# Planktoscope-Hat.net
KiCad netlist of a schematic drawn in EAGLE
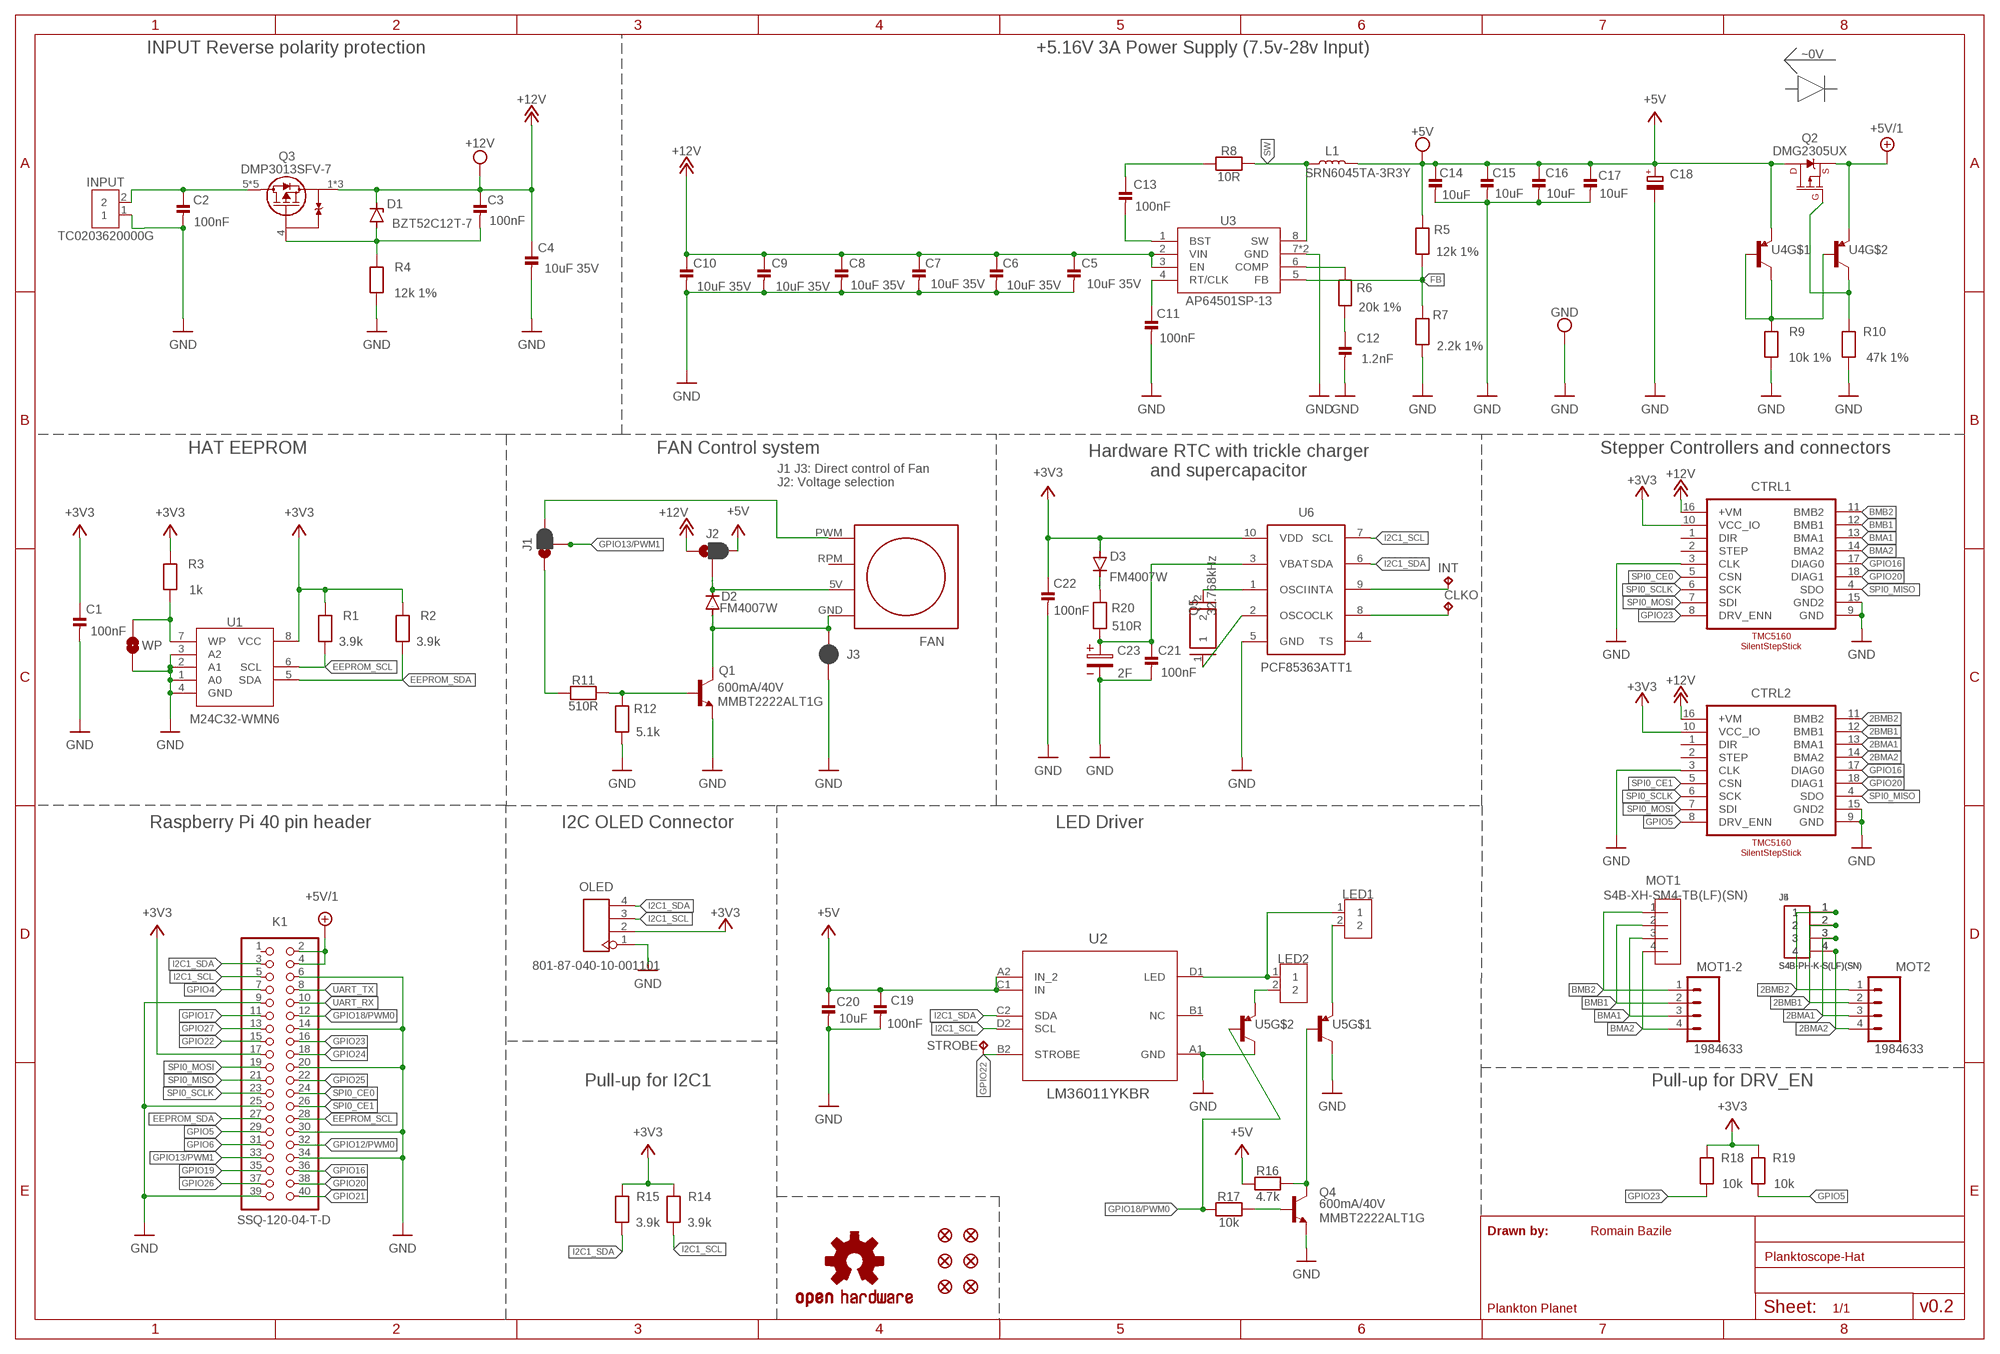
[diagram p0: schematic, sheet 1]

(export (version "E")
  (design (tool "Eeschema 10.0.6"))
  (components
    (comp (ref "+5V")
      (value "TESTPOINTPAD2MM")
      (footprint "eagle-import:TESTPOINT_PAD_2MM")
      (libsource (lib "eagle-import") (part "TESTPOINTPAD2MM"))
    )
    (comp (ref "+12V")
      (value "TESTPOINTPAD2MM")
      (footprint "eagle-import:TESTPOINT_PAD_2MM")
      (libsource (lib "eagle-import") (part "TESTPOINTPAD2MM"))
    )
    (comp (ref "C1")
      (value "100nF")
      (footprint "eagle-import:_0805MP")
      (libsource (lib "eagle-import") (part "CAP_CERAMIC_0805MP"))
    )
    (comp (ref "C2")
      (value "100nF")
      (footprint "eagle-import:_0805MP")
      (libsource (lib "eagle-import") (part "CAP_CERAMIC_0805MP"))
    )
    (comp (ref "C3")
      (value "100nF")
      (footprint "eagle-import:_0805MP")
      (libsource (lib "eagle-import") (part "CAP_CERAMIC_0805MP"))
    )
    (comp (ref "C4")
      (value "10uF 35V")
      (footprint "eagle-import:_0805MP")
      (libsource (lib "eagle-import") (part "CAP_CERAMIC_0805MP"))
    )
    (comp (ref "C5")
      (value "10uF 35V")
      (footprint "eagle-import:_0805MP")
      (libsource (lib "eagle-import") (part "CAP_CERAMIC_0805MP"))
    )
    (comp (ref "C6")
      (value "10uF 35V")
      (footprint "eagle-import:_0805MP")
      (libsource (lib "eagle-import") (part "CAP_CERAMIC_0805MP"))
    )
    (comp (ref "C7")
      (value "10uF 35V")
      (footprint "eagle-import:_0805MP")
      (libsource (lib "eagle-import") (part "CAP_CERAMIC_0805MP"))
    )
    (comp (ref "C8")
      (value "10uF 35V")
      (footprint "eagle-import:_0805MP")
      (libsource (lib "eagle-import") (part "CAP_CERAMIC_0805MP"))
    )
    (comp (ref "C9")
      (value "10uF 35V")
      (footprint "eagle-import:_0805MP")
      (libsource (lib "eagle-import") (part "CAP_CERAMIC_0805MP"))
    )
    (comp (ref "C10")
      (value "10uF 35V")
      (footprint "eagle-import:_0805MP")
      (libsource (lib "eagle-import") (part "CAP_CERAMIC_0805MP"))
    )
    (comp (ref "C11")
      (value "100nF")
      (footprint "eagle-import:_0805MP")
      (libsource (lib "eagle-import") (part "CAP_CERAMIC_0805MP"))
    )
    (comp (ref "C12")
      (value "1.2nF")
      (footprint "eagle-import:_0805MP")
      (libsource (lib "eagle-import") (part "CAP_CERAMIC_0805MP"))
    )
    (comp (ref "C13")
      (value "100nF")
      (footprint "eagle-import:_0805MP")
      (libsource (lib "eagle-import") (part "CAP_CERAMIC_0805MP"))
    )
    (comp (ref "C14")
      (value "10uF")
      (footprint "eagle-import:_0805MP")
      (libsource (lib "eagle-import") (part "CAP_CERAMIC_0805MP"))
    )
    (comp (ref "C15")
      (value "10uF")
      (footprint "eagle-import:_0805MP")
      (libsource (lib "eagle-import") (part "CAP_CERAMIC_0805MP"))
    )
    (comp (ref "C16")
      (value "10uF")
      (footprint "eagle-import:_0805MP")
      (libsource (lib "eagle-import") (part "CAP_CERAMIC_0805MP"))
    )
    (comp (ref "C17")
      (value "10uF")
      (footprint "eagle-import:_0805MP")
      (libsource (lib "eagle-import") (part "CAP_CERAMIC_0805MP"))
    )
    (comp (ref "C18")
      (value "100µF 10VDC")
      (footprint "eagle-import:CAPMP6032X280N")
      (fields (field (name "MPN") "TPSC107K010T0200"))
      (libsource (lib "eagle-import") (part "C-POLTANTALUM-2412(6032-METRIC)_"))
    )
    (comp (ref "C19")
      (value "100nF")
      (footprint "eagle-import:_0805MP")
      (libsource (lib "eagle-import") (part "CAP_CERAMIC_0805MP"))
    )
    (comp (ref "C20")
      (value "10uF")
      (footprint "eagle-import:_0805MP")
      (libsource (lib "eagle-import") (part "CAP_CERAMIC_0805MP"))
    )
    (comp (ref "C21")
      (value "100nF")
      (footprint "eagle-import:_0805MP")
      (libsource (lib "eagle-import") (part "CAP_CERAMIC_0805MP"))
    )
    (comp (ref "C22")
      (value "100nF")
      (footprint "eagle-import:_0805MP")
      (libsource (lib "eagle-import") (part "CAP_CERAMIC_0805MP"))
    )
    (comp (ref "C23")
      (value "2F")
      (footprint "eagle-import:8X3.5X0.9(DXAXB)")
      (fields (field (name "MPN") "SCCR12E105SRB"))
      (libsource (lib "eagle-import") (part "WCAP-PTHT_870135174001_8X8"))
    )
    (comp (ref "CLKO")
      (value "TPB1,27")
      (footprint "eagle-import:B1,27")
      (libsource (lib "eagle-import") (part "TPB1,27"))
    )
    (comp (ref "CTRL1")
      (value "TMC5160_SILENTSTEPSTICK")
      (footprint "eagle-import:TMC5160_STEPSTICK")
      (libsource (lib "eagle-import") (part "TMC5160_SILENTSTEPSTICK"))
    )
    (comp (ref "CTRL2")
      (value "TMC5160_SILENTSTEPSTICK")
      (footprint "eagle-import:TMC5160_STEPSTICK")
      (libsource (lib "eagle-import") (part "TMC5160_SILENTSTEPSTICK"))
    )
    (comp (ref "D1")
      (value "BZT52C12T-7")
      (footprint "eagle-import:SODFL1608X70")
      (libsource (lib "eagle-import") (part "ZENERSODFL(1608-METRIC)_"))
    )
    (comp (ref "D2")
      (value "FM4007W")
      (footprint "eagle-import:DO-214AC")
      (libsource (lib "eagle-import") (part "DIODE-DO-214AC"))
    )
    (comp (ref "D3")
      (value "FM4007W")
      (footprint "eagle-import:DO-214AC")
      (libsource (lib "eagle-import") (part "DIODE-DO-214AC"))
    )
    (comp (ref "FAN")
      (value "40MM_FAN")
      (footprint "eagle-import:40MM_FAN")
      (libsource (lib "eagle-import") (part "40MM_FAN"))
    )
    (comp (ref "FD1")
      (value "FIDUCIAL1X2")
      (footprint "eagle-import:FIDUCIAL-1X2")
      (libsource (lib "eagle-import") (part "FIDUCIAL1X2"))
    )
    (comp (ref "FD2")
      (value "FIDUCIAL1X2")
      (footprint "eagle-import:FIDUCIAL-1X2")
      (libsource (lib "eagle-import") (part "FIDUCIAL1X2"))
    )
    (comp (ref "FD3")
      (value "FIDUCIAL1X2")
      (footprint "eagle-import:FIDUCIAL-1X2")
      (libsource (lib "eagle-import") (part "FIDUCIAL1X2"))
    )
    (comp (ref "FD4")
      (value "FIDUCIAL1X2")
      (footprint "eagle-import:FIDUCIAL-1X2")
      (libsource (lib "eagle-import") (part "FIDUCIAL1X2"))
    )
    (comp (ref "FD5")
      (value "FIDUCIAL1X2")
      (footprint "eagle-import:FIDUCIAL-1X2")
      (libsource (lib "eagle-import") (part "FIDUCIAL1X2"))
    )
    (comp (ref "FD6")
      (value "FIDUCIAL1X2")
      (footprint "eagle-import:FIDUCIAL-1X2")
      (libsource (lib "eagle-import") (part "FIDUCIAL1X2"))
    )
    (comp (ref "GND")
      (value "TESTPOINTPAD2MM")
      (footprint "eagle-import:TESTPOINT_PAD_2MM")
      (libsource (lib "eagle-import") (part "TESTPOINTPAD2MM"))
    )
    (comp (ref "INPUT")
      (value "TC0203620000G")
      (footprint "eagle-import:TERMBLK_508-2N")
      (fields
        (field (name "MANUFACTURER") "TE Connectivity")
        (field (name "MPN") "282837-2")
        (field (name "MPN_1") "TC0203620000G")
      )
      (libsource (lib "eagle-import") (part "2828XX-2282837-2"))
    )
    (comp (ref "INT")
      (value "TPB1,27")
      (footprint "eagle-import:B1,27")
      (libsource (lib "eagle-import") (part "TPB1,27"))
    )
    (comp (ref "J1")
      (value "JUMPER-SMT_3_1-NC_PASTE_SILK")
      (footprint "eagle-import:SMT-JUMPER_3_1-NC_PASTE_SILK")
      (libsource (lib "eagle-import") (part "JUMPER-SMT_3_1-NC_PASTE_SILK"))
    )
    (comp (ref "J2")
      (value "JUMPER-SMT_3_1-NC_PASTE_SILK")
      (footprint "eagle-import:SMT-JUMPER_3_1-NC_PASTE_SILK")
      (libsource (lib "eagle-import") (part "JUMPER-SMT_3_1-NC_PASTE_SILK"))
    )
    (comp (ref "J3")
      (value "JUMPER-SMT_2_NC_PASTE_SILK")
      (footprint "eagle-import:SMT-JUMPER_2_NC_PASTE_SILK")
      (libsource (lib "eagle-import") (part "JUMPER-SMT_2_NC_PASTE_SILK"))
    )
    (comp (ref "J4")
      (value "S4B-PH-K-S(LF)(SN)")
      (footprint "eagle-import:S4B-PH-K-S(LF)(SN)")
      (fields
        (field (name "DIGIKEY_PARTNO") "455-1721-ND")
        (field (name "MANUFACTURER") "JST Sales America Inc.")
        (field (name "CREATED_BY") "PCBLayout.com")
      )
      (libsource (lib "eagle-import") (part "S4B-PH-K-S(LF)(SN)"))
    )
    (comp (ref "J5")
      (value "S4B-PH-K-S(LF)(SN)")
      (footprint "eagle-import:S4B-PH-K-S(LF)(SN)")
      (fields
        (field (name "DIGIKEY_PARTNO") "455-1721-ND")
        (field (name "MANUFACTURER") "JST Sales America Inc.")
        (field (name "CREATED_BY") "PCBLayout.com")
      )
      (libsource (lib "eagle-import") (part "S4B-PH-K-S(LF)(SN)"))
    )
    (comp (ref "K1")
      (value "SSQ-120-04-T-D")
      (footprint "eagle-import:2X20")
      (libsource (lib "eagle-import") (part "PINHD-2X20"))
    )
    (comp (ref "L1")
      (value "SRN6045TA-3R3Y")
      (footprint "eagle-import:SRN6045")
      (libsource (lib "eagle-import") (part "INDUCTOR-SRN6045-33UH"))
    )
    (comp (ref "LED1")
      (value "2828XX-2282834-2")
      (footprint "eagle-import:TERMBLK_254-2N")
      (libsource (lib "eagle-import") (part "2828XX-2282834-2"))
    )
    (comp (ref "LED2")
      (value "2828XX-2282834-2")
      (footprint "eagle-import:TERMBLK_254-2N")
      (libsource (lib "eagle-import") (part "2828XX-2282834-2"))
    )
    (comp (ref "LOGO1")
      (value "OSHW-LOGOL")
      (footprint "eagle-import:OSHW-LOGO-L")
      (libsource (lib "eagle-import") (part "OSHW-LOGOL"))
    )
    (comp (ref "MOT1")
      (value "S4B-XH-SM4-TB(LF)(SN)")
      (footprint "eagle-import:CONN_S4B-XH-SM4-TB_JST")
      (fields
        (field (name "MPN") "S4B-XH-SM4-TB(LF)(SN)")
        (field (name "COPYRIGHT") "Copyright (C) 2018 Accelerated Designs. All rights reserved")
      )
      (libsource (lib "eagle-import") (part "S4B-XH-SM4-TB(LF)(SN)"))
    )
    (comp (ref "MOT1-2")
      (value "1984633")
      (footprint "eagle-import:SCREWTERMINAL-3.5MM-4")
      (libsource (lib "eagle-import") (part "CONN_04SCREW"))
    )
    (comp (ref "MOT2")
      (value "1984633")
      (footprint "eagle-import:SCREWTERMINAL-3.5MM-4")
      (libsource (lib "eagle-import") (part "CONN_04SCREW"))
    )
    (comp (ref "OLED")
      (value "801-87-040-10-001101")
      (footprint "eagle-import:H4-2.54")
      (fields (field (name "MPN") "P125-1104A0BS116A1"))
      (libsource (lib "eagle-import") (part "DIP-BLACK-MALE-HEADER-VERT(4P-2.54)"))
    )
    (comp (ref "Q1")
      (value "600mA/40V")
      (footprint "eagle-import:SOT23-3")
      (fields (field (name "MPN") "MMBT2222ALT1G"))
      (libsource (lib "eagle-import") (part "TRANS_NPN-MMBT2222AL"))
    )
    (comp (ref "Q2")
      (value "DMG2305UX")
      (footprint "eagle-import:SOT23-3")
      (libsource (lib "eagle-import") (part "MOSFET_PCH-DMG2305UX-7"))
    )
    (comp (ref "Q3")
      (value "DMP3013SFV-7")
      (footprint "eagle-import:POWERDI3333-8_UX_DIO")
      (fields
        (field (name "ALT_MANUFACTURE_PART_NUMBER") "SI7101DN")
        (field (name "COPYRIGHT") "Copyright (C) 2018 Accelerated Designs. All rights reserved")
      )
      (libsource (lib "eagle-import") (part "DMP3013SFV-7"))
    )
    (comp (ref "Q4")
      (value "600mA/40V")
      (footprint "eagle-import:SOT23-3")
      (fields (field (name "MPN") "MMBT2222ALT1G"))
      (libsource (lib "eagle-import") (part "TRANS_NPN-MMBT2222AL"))
    )
    (comp (ref "Q5")
      (value "32.768kHz")
      (footprint "eagle-import:XTAL_ABS07-32.768KHZ-T")
      (fields (field (name "MANUFACTURER") "Abracon LLC") (field (name "MPN") "ABS07-32.768KHZ-T "))
      (libsource (lib "eagle-import") (part "ABSO7"))
    )
    (comp (ref "R1")
      (value "3.9k")
      (footprint "eagle-import:_0805MP")
      (libsource (lib "eagle-import") (part "RESISTOR_0805MP"))
    )
    (comp (ref "R2")
      (value "3.9k")
      (footprint "eagle-import:_0805MP")
      (libsource (lib "eagle-import") (part "RESISTOR_0805MP"))
    )
    (comp (ref "R3")
      (value "1k")
      (footprint "eagle-import:_0805MP")
      (libsource (lib "eagle-import") (part "RESISTOR_0805MP"))
    )
    (comp (ref "R4")
      (value "12k 1%")
      (footprint "eagle-import:_0805MP")
      (libsource (lib "eagle-import") (part "RESISTOR_0805MP"))
    )
    (comp (ref "R5")
      (value "12k 1%")
      (footprint "eagle-import:_0805MP")
      (libsource (lib "eagle-import") (part "RESISTOR_0805MP"))
    )
    (comp (ref "R6")
      (value "20k 1%")
      (footprint "eagle-import:_0805MP")
      (libsource (lib "eagle-import") (part "RESISTOR_0805MP"))
    )
    (comp (ref "R7")
      (value "2.2k 1%")
      (footprint "eagle-import:_0805MP")
      (libsource (lib "eagle-import") (part "RESISTOR_0805MP"))
    )
    (comp (ref "R8")
      (value "10R")
      (footprint "eagle-import:_0805MP")
      (libsource (lib "eagle-import") (part "RESISTOR_0805MP"))
    )
    (comp (ref "R9")
      (value "10k 1%")
      (footprint "eagle-import:_0805MP")
      (libsource (lib "eagle-import") (part "RESISTOR_0805MP"))
    )
    (comp (ref "R10")
      (value "47k 1%")
      (footprint "eagle-import:_0805MP")
      (libsource (lib "eagle-import") (part "RESISTOR_0805MP"))
    )
    (comp (ref "R11")
      (value "510R")
      (footprint "eagle-import:_0805MP")
      (libsource (lib "eagle-import") (part "RESISTOR_0805MP"))
    )
    (comp (ref "R12")
      (value "5.1k")
      (footprint "eagle-import:_0805MP")
      (libsource (lib "eagle-import") (part "RESISTOR_0805MP"))
    )
    (comp (ref "R14")
      (value "3.9k")
      (footprint "eagle-import:_0805MP")
      (libsource (lib "eagle-import") (part "RESISTOR_0805MP"))
    )
    (comp (ref "R15")
      (value "3.9k")
      (footprint "eagle-import:_0805MP")
      (libsource (lib "eagle-import") (part "RESISTOR_0805MP"))
    )
    (comp (ref "R16")
      (value "4.7k")
      (footprint "eagle-import:_0805MP")
      (libsource (lib "eagle-import") (part "RESISTOR_0805MP"))
    )
    (comp (ref "R17")
      (value "10k")
      (footprint "eagle-import:_0805MP")
      (libsource (lib "eagle-import") (part "RESISTOR_0805MP"))
    )
    (comp (ref "R18")
      (value "10k")
      (footprint "eagle-import:_0805MP")
      (libsource (lib "eagle-import") (part "RESISTOR_0805MP"))
    )
    (comp (ref "R19")
      (value "10k")
      (footprint "eagle-import:_0805MP")
      (libsource (lib "eagle-import") (part "RESISTOR_0805MP"))
    )
    (comp (ref "R20")
      (value "510R")
      (footprint "eagle-import:_0805MP")
      (libsource (lib "eagle-import") (part "RESISTOR_0805MP"))
    )
    (comp (ref "STROBE")
      (value "TPTP15R")
      (footprint "eagle-import:TP15R")
      (libsource (lib "eagle-import") (part "TPTP15R"))
    )
    (comp (ref "U1")
      (value "M24C32-WMN6")
      (footprint "eagle-import:SO-8_STM")
      (libsource (lib "eagle-import") (part "M24C32-WMN6"))
    )
    (comp (ref "U2")
      (value "LM36011YKBR")
      (footprint "eagle-import:YKB0008AGAG")
      (fields (field (name "MANUFACTURER") "Texas Instruments"))
      (libsource (lib "eagle-import") (part "LM36011YKBR"))
    )
    (comp (ref "U3")
      (value "AP64501SP-13")
      (footprint "eagle-import:SO-8EP_DIO")
      (fields
        (field (name "MANUFACTURER_PART_NUMBER") "AP64500SP-13")
        (field (name "COPYRIGHT") "Copyright (C) 2018 Accelerated Designs. All rights reserved")
      )
      (libsource (lib "eagle-import") (part "AP64500SP-13"))
    )
    (comp (ref "U4")
      (value "TRANS_PNP_DUAL")
      (footprint "eagle-import:SOT363")
      (libsource (lib "eagle-import") (part "TRANS_PNP_DUAL"))
    )
    (comp (ref "U5")
      (value "TRANS_PNP_DUAL")
      (footprint "eagle-import:SOT363")
      (libsource (lib "eagle-import") (part "TRANS_PNP_DUAL"))
    )
    (comp (ref "U6")
      (value "PCF85363ATT1")
      (footprint "eagle-import:SOP50P590X90-10N")
      (libsource (lib "eagle-import") (part "PCF85363ATT1"))
    )
    (comp (ref "WP")
      (value "JUMPER-SMT_2_NO_SILK")
      (footprint "eagle-import:SMT-JUMPER_2_NO_SILK")
      (libsource (lib "eagle-import") (part "JUMPER-SMT_2_NO_SILK"))
    )
  )
  (nets
    (net (code "1") (name "+3V3") (class "Default")
      (node (ref "C1") (pin "1") (pinfunction "1_1") (pintype "passive"))
      (node (ref "C22") (pin "1") (pinfunction "1_1") (pintype "passive"))
      (node (ref "CTRL1") (pin "10") (pinfunction "VCC_IO_10") (pintype "passive"))
      (node (ref "CTRL2") (pin "10") (pinfunction "VCC_IO_10") (pintype "passive"))
      (node (ref "D3") (pin "A") (pinfunction "A_A") (pintype "passive"))
      (node (ref "K1") (pin "17") (pinfunction "17_17") (pintype "passive"))
      (node (ref "OLED") (pin "2") (pinfunction "P$2_2") (pintype "bidirectional"))
      (node (ref "R1") (pin "2") (pinfunction "2_2") (pintype "passive"))
      (node (ref "R14") (pin "2") (pinfunction "2_2") (pintype "passive"))
      (node (ref "R15") (pin "2") (pinfunction "2_2") (pintype "passive"))
      (node (ref "R18") (pin "2") (pinfunction "2_2") (pintype "passive"))
      (node (ref "R19") (pin "2") (pinfunction "2_2") (pintype "passive"))
      (node (ref "R2") (pin "2") (pinfunction "2_2") (pintype "passive"))
      (node (ref "R3") (pin "2") (pinfunction "2_2") (pintype "passive"))
      (node (ref "U1") (pin "8") (pinfunction "VCC_8") (pintype "power_in"))
      (node (ref "U6") (pin "10") (pinfunction "VDD_10") (pintype "bidirectional"))
    )
    (net (code "2") (name "+5V") (class "Default")
      (node (ref "+5V") (pin "P$1") (pinfunction "P$1_P$1") (pintype "bidirectional"))
      (node (ref "C14") (pin "1") (pinfunction "1_1") (pintype "passive"))
      (node (ref "C15") (pin "1") (pinfunction "1_1") (pintype "passive"))
      (node (ref "C16") (pin "1") (pinfunction "1_1") (pintype "passive"))
      (node (ref "C17") (pin "1") (pinfunction "1_1") (pintype "passive"))
      (node (ref "C18") (pin "1") (pinfunction "+_1") (pintype "passive"))
      (node (ref "C19") (pin "1") (pinfunction "1_1") (pintype "passive"))
      (node (ref "C20") (pin "1") (pinfunction "1_1") (pintype "passive"))
      (node (ref "J2") (pin "3") (pinfunction "3_3") (pintype "passive"))
      (node (ref "L1") (pin "2") (pinfunction "2_2") (pintype "passive"))
      (node (ref "Q2") (pin "3") (pinfunction "D_3") (pintype "bidirectional"))
      (node (ref "R16") (pin "2") (pinfunction "2_2") (pintype "passive"))
      (node (ref "R5") (pin "2") (pinfunction "2_2") (pintype "passive"))
      (node (ref "U2") (pin "A2") (pinfunction "IN_2_A2") (pintype "power_in"))
      (node (ref "U2") (pin "C1") (pinfunction "IN_C1") (pintype "power_in"))
      (node (ref "U4") (pin "1") (pinfunction "E_1") (pintype "passive"))
    )
    (net (code "3") (name "+5V{slash}1") (class "Default")
      (node (ref "K1") (pin "2") (pinfunction "2_2") (pintype "passive"))
      (node (ref "K1") (pin "4") (pinfunction "4_4") (pintype "passive"))
      (node (ref "Q2") (pin "2") (pinfunction "S_2") (pintype "bidirectional"))
      (node (ref "U4") (pin "4") (pinfunction "E_4") (pintype "passive"))
    )
    (net (code "4") (name "+12V") (class "Default")
      (node (ref "+12V") (pin "P$1") (pinfunction "P$1_P$1") (pintype "bidirectional"))
      (node (ref "C10") (pin "1") (pinfunction "1_1") (pintype "passive"))
      (node (ref "C3") (pin "1") (pinfunction "1_1") (pintype "passive"))
      (node (ref "C4") (pin "1") (pinfunction "1_1") (pintype "passive"))
      (node (ref "C5") (pin "1") (pinfunction "1_1") (pintype "passive"))
      (node (ref "C6") (pin "1") (pinfunction "1_1") (pintype "passive"))
      (node (ref "C7") (pin "1") (pinfunction "1_1") (pintype "passive"))
      (node (ref "C8") (pin "1") (pinfunction "1_1") (pintype "passive"))
      (node (ref "C9") (pin "1") (pinfunction "1_1") (pintype "passive"))
      (node (ref "CTRL1") (pin "16") (pinfunction "+VM_16") (pintype "passive"))
      (node (ref "CTRL2") (pin "16") (pinfunction "+VM_16") (pintype "passive"))
      (node (ref "D1") (pin "1") (pinfunction "C_1") (pintype "passive"))
      (node (ref "J2") (pin "1") (pinfunction "1_1") (pintype "passive"))
      (node (ref "Q3") (pin "1") (pinfunction "S_1") (pintype "passive"))
      (node (ref "Q3") (pin "2") (pinfunction "S_2") (pintype "passive"))
      (node (ref "Q3") (pin "3") (pinfunction "S_3") (pintype "passive"))
      (node (ref "U3") (pin "2") (pinfunction "VIN_2") (pintype "power_in"))
      (node (ref "U3") (pin "3") (pinfunction "EN_3") (pintype "input"))
    )
    (net (code "5") (name "2BMA1") (class "Default")
      (node (ref "CTRL2") (pin "13") (pinfunction "BMA1_13") (pintype "passive"))
      (node (ref "J4") (pin "3") (pinfunction "3_3") (pintype "passive"))
      (node (ref "J5") (pin "3") (pinfunction "3_3") (pintype "passive"))
      (node (ref "MOT2") (pin "3") (pinfunction "3_3") (pintype "passive"))
    )
    (net (code "6") (name "2BMA2") (class "Default")
      (node (ref "CTRL2") (pin "14") (pinfunction "BMA2_14") (pintype "passive"))
      (node (ref "J4") (pin "4") (pinfunction "4_4") (pintype "passive"))
      (node (ref "J5") (pin "4") (pinfunction "4_4") (pintype "passive"))
      (node (ref "MOT2") (pin "4") (pinfunction "4_4") (pintype "passive"))
    )
    (net (code "7") (name "2BMB1") (class "Default")
      (node (ref "CTRL2") (pin "12") (pinfunction "BMB1_12") (pintype "passive"))
      (node (ref "J4") (pin "2") (pinfunction "2_2") (pintype "passive"))
      (node (ref "J5") (pin "2") (pinfunction "2_2") (pintype "passive"))
      (node (ref "MOT2") (pin "2") (pinfunction "2_2") (pintype "passive"))
    )
    (net (code "8") (name "2BMB2") (class "Default")
      (node (ref "CTRL2") (pin "11") (pinfunction "BMB2_11") (pintype "passive"))
      (node (ref "J4") (pin "1") (pinfunction "1_1") (pintype "passive"))
      (node (ref "J5") (pin "1") (pinfunction "1_1") (pintype "passive"))
      (node (ref "MOT2") (pin "1") (pinfunction "1_1") (pintype "passive"))
    )
    (net (code "9") (name "BMA1") (class "Default")
      (node (ref "CTRL1") (pin "13") (pinfunction "BMA1_13") (pintype "passive"))
      (node (ref "MOT1") (pin "3") (pinfunction "3_3") (pintype "passive"))
      (node (ref "MOT1-2") (pin "3") (pinfunction "3_3") (pintype "passive"))
    )
    (net (code "10") (name "BMA2") (class "Default")
      (node (ref "CTRL1") (pin "14") (pinfunction "BMA2_14") (pintype "passive"))
      (node (ref "MOT1") (pin "4") (pinfunction "4_4") (pintype "passive"))
      (node (ref "MOT1-2") (pin "4") (pinfunction "4_4") (pintype "passive"))
    )
    (net (code "11") (name "BMB1") (class "Default")
      (node (ref "CTRL1") (pin "12") (pinfunction "BMB1_12") (pintype "passive"))
      (node (ref "MOT1") (pin "2") (pinfunction "2_2") (pintype "passive"))
      (node (ref "MOT1-2") (pin "2") (pinfunction "2_2") (pintype "passive"))
    )
    (net (code "12") (name "BMB2") (class "Default")
      (node (ref "CTRL1") (pin "11") (pinfunction "BMB2_11") (pintype "passive"))
      (node (ref "MOT1") (pin "1") (pinfunction "1_1") (pintype "passive"))
      (node (ref "MOT1-2") (pin "1") (pinfunction "1_1") (pintype "passive"))
    )
    (net (code "13") (name "EEPROM_SCL") (class "Default")
      (node (ref "K1") (pin "28") (pinfunction "28_28") (pintype "passive"))
      (node (ref "R1") (pin "1") (pinfunction "1_1") (pintype "passive"))
      (node (ref "U1") (pin "6") (pinfunction "SCL_6") (pintype "input"))
    )
    (net (code "14") (name "EEPROM_SDA") (class "Default")
      (node (ref "K1") (pin "27") (pinfunction "27_27") (pintype "passive"))
      (node (ref "R2") (pin "1") (pinfunction "1_1") (pintype "passive"))
      (node (ref "U1") (pin "5") (pinfunction "SDA_5") (pintype "bidirectional"))
    )
    (net (code "15") (name "FB") (class "Default")
      (node (ref "R5") (pin "1") (pinfunction "1_1") (pintype "passive"))
      (node (ref "R7") (pin "2") (pinfunction "2_2") (pintype "passive"))
      (node (ref "U3") (pin "5") (pinfunction "FB_5") (pintype "passive"))
    )
    (net (code "16") (name "GND") (class "Default")
      (node (ref "C1") (pin "2") (pinfunction "2_2") (pintype "passive"))
      (node (ref "C10") (pin "2") (pinfunction "2_2") (pintype "passive"))
      (node (ref "C11") (pin "2") (pinfunction "2_2") (pintype "passive"))
      (node (ref "C12") (pin "2") (pinfunction "2_2") (pintype "passive"))
      (node (ref "C14") (pin "2") (pinfunction "2_2") (pintype "passive"))
      (node (ref "C15") (pin "2") (pinfunction "2_2") (pintype "passive"))
      (node (ref "C16") (pin "2") (pinfunction "2_2") (pintype "passive"))
      (node (ref "C17") (pin "2") (pinfunction "2_2") (pintype "passive"))
      (node (ref "C18") (pin "2") (pinfunction "-_2") (pintype "passive"))
      (node (ref "C19") (pin "2") (pinfunction "2_2") (pintype "passive"))
      (node (ref "C2") (pin "2") (pinfunction "2_2") (pintype "passive"))
      (node (ref "C20") (pin "2") (pinfunction "2_2") (pintype "passive"))
      (node (ref "C21") (pin "2") (pinfunction "2_2") (pintype "passive"))
      (node (ref "C22") (pin "2") (pinfunction "2_2") (pintype "passive"))
      (node (ref "C23") (pin "2") (pinfunction "2_2") (pintype "passive"))
      (node (ref "C4") (pin "2") (pinfunction "2_2") (pintype "passive"))
      (node (ref "C5") (pin "2") (pinfunction "2_2") (pintype "passive"))
      (node (ref "C6") (pin "2") (pinfunction "2_2") (pintype "passive"))
      (node (ref "C7") (pin "2") (pinfunction "2_2") (pintype "passive"))
      (node (ref "C8") (pin "2") (pinfunction "2_2") (pintype "passive"))
      (node (ref "C9") (pin "2") (pinfunction "2_2") (pintype "passive"))
      (node (ref "CTRL1") (pin "15") (pinfunction "GND2_15") (pintype "passive"))
      (node (ref "CTRL1") (pin "3") (pinfunction "CLK_3") (pintype "passive"))
      (node (ref "CTRL1") (pin "9") (pinfunction "GND_9") (pintype "passive"))
      (node (ref "CTRL2") (pin "15") (pinfunction "GND2_15") (pintype "passive"))
      (node (ref "CTRL2") (pin "3") (pinfunction "CLK_3") (pintype "passive"))
      (node (ref "CTRL2") (pin "9") (pinfunction "GND_9") (pintype "passive"))
      (node (ref "GND") (pin "P$1") (pinfunction "P$1_P$1") (pintype "bidirectional"))
      (node (ref "INPUT") (pin "1") (pinfunction "1_1") (pintype "bidirectional"))
      (node (ref "J3") (pin "1") (pinfunction "1_1") (pintype "passive"))
      (node (ref "K1") (pin "14") (pinfunction "14_14") (pintype "passive"))
      (node (ref "K1") (pin "20") (pinfunction "20_20") (pintype "passive"))
      (node (ref "K1") (pin "25") (pinfunction "25_25") (pintype "passive"))
      (node (ref "K1") (pin "30") (pinfunction "30_30") (pintype "passive"))
      (node (ref "K1") (pin "34") (pinfunction "34_34") (pintype "passive"))
      (node (ref "K1") (pin "39") (pinfunction "39_39") (pintype "passive"))
      (node (ref "K1") (pin "6") (pinfunction "6_6") (pintype "passive"))
      (node (ref "K1") (pin "9") (pinfunction "9_9") (pintype "passive"))
      (node (ref "OLED") (pin "1") (pinfunction "P$1_1") (pintype "bidirectional"))
      (node (ref "Q1") (pin "2") (pinfunction "E_2") (pintype "passive"))
      (node (ref "Q4") (pin "2") (pinfunction "E_2") (pintype "passive"))
      (node (ref "R10") (pin "1") (pinfunction "1_1") (pintype "passive"))
      (node (ref "R12") (pin "1") (pinfunction "1_1") (pintype "passive"))
      (node (ref "R4") (pin "1") (pinfunction "1_1") (pintype "passive"))
      (node (ref "R7") (pin "1") (pinfunction "1_1") (pintype "passive"))
      (node (ref "R9") (pin "1") (pinfunction "1_1") (pintype "passive"))
      (node (ref "U1") (pin "1") (pinfunction "A0_1") (pintype "input"))
      (node (ref "U1") (pin "2") (pinfunction "A1_2") (pintype "input"))
      (node (ref "U1") (pin "3") (pinfunction "A2_3") (pintype "input"))
      (node (ref "U1") (pin "4") (pinfunction "GND_4") (pintype "power_in"))
      (node (ref "U2") (pin "A1") (pinfunction "GND_A1") (pintype "power_in"))
      (node (ref "U3") (pin "7") (pinfunction "GND_7") (pintype "passive"))
      (node (ref "U3") (pin "EPAD") (pinfunction "GND_EPAD") (pintype "passive"))
      (node (ref "U5") (pin "3") (pinfunction "C_3") (pintype "passive"))
      (node (ref "U5") (pin "6") (pinfunction "C_6") (pintype "passive"))
      (node (ref "U6") (pin "5") (pinfunction "GND_5") (pintype "bidirectional"))
      (node (ref "WP") (pin "1") (pinfunction "1_1") (pintype "passive"))
    )
    (net (code "17") (name "GPIO4") (class "Default")
      (node (ref "K1") (pin "7") (pinfunction "7_7") (pintype "passive"))
    )
    (net (code "18") (name "GPIO5") (class "Default")
      (node (ref "CTRL2") (pin "8") (pinfunction "DRV_ENN_8") (pintype "passive"))
      (node (ref "K1") (pin "29") (pinfunction "29_29") (pintype "passive"))
      (node (ref "R19") (pin "1") (pinfunction "1_1") (pintype "passive"))
    )
    (net (code "19") (name "GPIO6") (class "Default")
      (node (ref "K1") (pin "31") (pinfunction "31_31") (pintype "passive"))
    )
    (net (code "20") (name "GPIO12{slash}PWM0") (class "Default")
      (node (ref "K1") (pin "32") (pinfunction "32_32") (pintype "passive"))
    )
    (net (code "21") (name "GPIO13{slash}PWM1") (class "Default")
      (node (ref "J1") (pin "2") (pinfunction "2_2") (pintype "passive"))
      (node (ref "K1") (pin "33") (pinfunction "33_33") (pintype "passive"))
    )
    (net (code "22") (name "GPIO16") (class "Default")
      (node (ref "CTRL1") (pin "17") (pinfunction "DIAG0_17") (pintype "passive"))
      (node (ref "CTRL2") (pin "17") (pinfunction "DIAG0_17") (pintype "passive"))
      (node (ref "K1") (pin "36") (pinfunction "36_36") (pintype "passive"))
    )
    (net (code "23") (name "GPIO17") (class "Default")
      (node (ref "K1") (pin "11") (pinfunction "11_11") (pintype "passive"))
    )
    (net (code "24") (name "GPIO18{slash}PWM0") (class "Default")
      (node (ref "K1") (pin "12") (pinfunction "12_12") (pintype "passive"))
      (node (ref "R17") (pin "1") (pinfunction "1_1") (pintype "passive"))
      (node (ref "U5") (pin "5") (pinfunction "B_5") (pintype "passive"))
    )
    (net (code "25") (name "GPIO19") (class "Default")
      (node (ref "K1") (pin "35") (pinfunction "35_35") (pintype "passive"))
    )
    (net (code "26") (name "GPIO20") (class "Default")
      (node (ref "CTRL1") (pin "18") (pinfunction "DIAG1_18") (pintype "passive"))
      (node (ref "CTRL2") (pin "18") (pinfunction "DIAG1_18") (pintype "passive"))
      (node (ref "K1") (pin "38") (pinfunction "38_38") (pintype "passive"))
    )
    (net (code "27") (name "GPIO21") (class "Default")
      (node (ref "K1") (pin "40") (pinfunction "40_40") (pintype "passive"))
    )
    (net (code "28") (name "GPIO22") (class "Default")
      (node (ref "K1") (pin "15") (pinfunction "15_15") (pintype "passive"))
      (node (ref "STROBE") (pin "TP") (pinfunction "TP_TP") (pintype "input"))
      (node (ref "U2") (pin "B2") (pinfunction "STROBE_B2") (pintype "input"))
    )
    (net (code "29") (name "GPIO23") (class "Default")
      (node (ref "CTRL1") (pin "8") (pinfunction "DRV_ENN_8") (pintype "passive"))
      (node (ref "K1") (pin "16") (pinfunction "16_16") (pintype "passive"))
      (node (ref "R18") (pin "1") (pinfunction "1_1") (pintype "passive"))
    )
    (net (code "30") (name "GPIO24") (class "Default")
      (node (ref "K1") (pin "18") (pinfunction "18_18") (pintype "passive"))
    )
    (net (code "31") (name "GPIO25") (class "Default")
      (node (ref "K1") (pin "22") (pinfunction "22_22") (pintype "passive"))
    )
    (net (code "32") (name "GPIO26") (class "Default")
      (node (ref "K1") (pin "37") (pinfunction "37_37") (pintype "passive"))
    )
    (net (code "33") (name "GPIO27") (class "Default")
      (node (ref "K1") (pin "13") (pinfunction "13_13") (pintype "passive"))
    )
    (net (code "34") (name "I2C1_SCL") (class "Default")
      (node (ref "K1") (pin "5") (pinfunction "5_5") (pintype "passive"))
      (node (ref "OLED") (pin "3") (pinfunction "P$3_3") (pintype "bidirectional"))
      (node (ref "R14") (pin "1") (pinfunction "1_1") (pintype "passive"))
      (node (ref "U2") (pin "D2") (pinfunction "SCL_D2") (pintype "input"))
      (node (ref "U6") (pin "7") (pinfunction "SCL_7") (pintype "bidirectional"))
    )
    (net (code "35") (name "I2C1_SDA") (class "Default")
      (node (ref "K1") (pin "3") (pinfunction "3_3") (pintype "passive"))
      (node (ref "OLED") (pin "4") (pinfunction "P$4_4") (pintype "bidirectional"))
      (node (ref "R15") (pin "1") (pinfunction "1_1") (pintype "passive"))
      (node (ref "U2") (pin "C2") (pinfunction "SDA_C2") (pintype "bidirectional"))
      (node (ref "U6") (pin "6") (pinfunction "SDA_6") (pintype "bidirectional"))
    )
    (net (code "36") (name "Net-(C2-Pad1)") (class "Default")
      (node (ref "C2") (pin "1") (pinfunction "1_1") (pintype "passive"))
      (node (ref "INPUT") (pin "2") (pinfunction "2_2") (pintype "bidirectional"))
      (node (ref "Q3") (pin "5") (pinfunction "D_5") (pintype "passive"))
      (node (ref "Q3") (pin "6") (pinfunction "D_6") (pintype "passive"))
      (node (ref "Q3") (pin "7") (pinfunction "D_7") (pintype "passive"))
      (node (ref "Q3") (pin "8") (pinfunction "D_8") (pintype "passive"))
      (node (ref "Q3") (pin "9") (pinfunction "D_9") (pintype "passive"))
    )
    (net (code "37") (name "Net-(C12-Pad1)") (class "Default")
      (node (ref "C12") (pin "1") (pinfunction "1_1") (pintype "passive"))
      (node (ref "R6") (pin "1") (pinfunction "1_1") (pintype "passive"))
    )
    (net (code "38") (name "Net-(C13-Pad1)") (class "Default")
      (node (ref "C13") (pin "1") (pinfunction "1_1") (pintype "passive"))
      (node (ref "R8") (pin "2") (pinfunction "2_2") (pintype "passive"))
    )
    (net (code "39") (name "Net-(D1-A)") (class "Default")
      (node (ref "C3") (pin "2") (pinfunction "2_2") (pintype "passive"))
      (node (ref "D1") (pin "2") (pinfunction "A_2") (pintype "passive"))
      (node (ref "Q3") (pin "4") (pinfunction "G_4") (pintype "passive"))
      (node (ref "R4") (pin "2") (pinfunction "2_2") (pintype "passive"))
    )
    (net (code "40") (name "Net-(D3-PadC)") (class "Default")
      (node (ref "D3") (pin "C") (pinfunction "C_C") (pintype "passive"))
      (node (ref "R20") (pin "2") (pinfunction "2_2") (pintype "passive"))
    )
    (net (code "41") (name "Net-(FAN-+5V)") (class "Default")
      (node (ref "D2") (pin "C") (pinfunction "C_C") (pintype "passive"))
      (node (ref "FAN") (pin "5V") (pinfunction "+5V_5V") (pintype "passive"))
      (node (ref "J2") (pin "2") (pinfunction "2_2") (pintype "passive"))
    )
    (net (code "42") (name "Net-(FAN-PadPWM)") (class "Default")
      (node (ref "FAN") (pin "PWM") (pinfunction "PWM_PWM") (pintype "passive"))
      (node (ref "J1") (pin "3") (pinfunction "3_3") (pintype "passive"))
    )
    (net (code "43") (name "Net-(J1-Pad1)") (class "Default")
      (node (ref "J1") (pin "1") (pinfunction "1_1") (pintype "passive"))
      (node (ref "R11") (pin "1") (pinfunction "1_1") (pintype "passive"))
    )
    (net (code "44") (name "Net-(Q1-B)") (class "Default")
      (node (ref "Q1") (pin "1") (pinfunction "B_1") (pintype "passive"))
      (node (ref "R11") (pin "2") (pinfunction "2_2") (pintype "passive"))
      (node (ref "R12") (pin "2") (pinfunction "2_2") (pintype "passive"))
    )
    (net (code "45") (name "Net-(Q1-C)") (class "Default")
      (node (ref "D2") (pin "A") (pinfunction "A_A") (pintype "passive"))
      (node (ref "FAN") (pin "GND") (pinfunction "GND_GND") (pintype "passive"))
      (node (ref "J3") (pin "2") (pinfunction "2_2") (pintype "passive"))
      (node (ref "Q1") (pin "3") (pinfunction "C_3") (pintype "passive"))
    )
    (net (code "46") (name "Net-(Q2-G)") (class "Default")
      (node (ref "Q2") (pin "1") (pinfunction "G_1") (pintype "bidirectional"))
      (node (ref "R10") (pin "2") (pinfunction "2_2") (pintype "passive"))
      (node (ref "U4") (pin "3") (pinfunction "C_3") (pintype "passive"))
    )
    (net (code "47") (name "Net-(Q4-B)") (class "Default")
      (node (ref "Q4") (pin "1") (pinfunction "B_1") (pintype "passive"))
      (node (ref "R17") (pin "2") (pinfunction "2_2") (pintype "passive"))
    )
    (net (code "48") (name "Net-(Q4-C)") (class "Default")
      (node (ref "Q4") (pin "3") (pinfunction "C_3") (pintype "passive"))
      (node (ref "R16") (pin "1") (pinfunction "1_1") (pintype "passive"))
      (node (ref "U5") (pin "2") (pinfunction "B_2") (pintype "passive"))
    )
    (net (code "49") (name "Net-(U1-WP)") (class "Default")
      (node (ref "R3") (pin "1") (pinfunction "1_1") (pintype "passive"))
      (node (ref "U1") (pin "7") (pinfunction "WP_7") (pintype "input"))
      (node (ref "WP") (pin "2") (pinfunction "2_2") (pintype "passive"))
    )
    (net (code "50") (name "Net-(U2-LED)") (class "Default")
      (node (ref "LED1") (pin "1") (pinfunction "1_1") (pintype "bidirectional"))
      (node (ref "LED2") (pin "1") (pinfunction "1_1") (pintype "bidirectional"))
      (node (ref "U2") (pin "D1") (pinfunction "LED_D1") (pintype "power_in"))
    )
    (net (code "51") (name "Net-(U3-BST)") (class "Default")
      (node (ref "C13") (pin "2") (pinfunction "2_2") (pintype "passive"))
      (node (ref "U3") (pin "1") (pinfunction "BST_1") (pintype "power_in"))
    )
    (net (code "52") (name "Net-(U3-COMP)") (class "Default")
      (node (ref "R6") (pin "2") (pinfunction "2_2") (pintype "passive"))
      (node (ref "U3") (pin "6") (pinfunction "COMP_6") (pintype "passive"))
    )
    (net (code "53") (name "Net-(U3-RT{slash}CLK)") (class "Default")
      (node (ref "C11") (pin "1") (pinfunction "1_1") (pintype "passive"))
      (node (ref "U3") (pin "4") (pinfunction "RT/CLK_4") (pintype "passive"))
    )
    (net (code "54") (name "Net-(U4A-B)") (class "Default")
      (node (ref "R9") (pin "2") (pinfunction "2_2") (pintype "passive"))
      (node (ref "U4") (pin "2") (pinfunction "B_2") (pintype "passive"))
      (node (ref "U4") (pin "5") (pinfunction "B_5") (pintype "passive"))
      (node (ref "U4") (pin "6") (pinfunction "C_6") (pintype "passive"))
    )
    (net (code "55") (name "Net-(U5A-E)") (class "Default")
      (node (ref "LED1") (pin "2") (pinfunction "2_2") (pintype "bidirectional"))
      (node (ref "U5") (pin "1") (pinfunction "E_1") (pintype "passive"))
    )
    (net (code "56") (name "Net-(U5B-E)") (class "Default")
      (node (ref "LED2") (pin "2") (pinfunction "2_2") (pintype "bidirectional"))
      (node (ref "U5") (pin "4") (pinfunction "E_4") (pintype "passive"))
    )
    (net (code "57") (name "Net-(U6-CLK)") (class "Default")
      (node (ref "CLKO") (pin "TP") (pinfunction "TP_TP") (pintype "input"))
      (node (ref "U6") (pin "8") (pinfunction "CLK_8") (pintype "bidirectional"))
    )
    (net (code "58") (name "Net-(U6-INTA)") (class "Default")
      (node (ref "INT") (pin "TP") (pinfunction "TP_TP") (pintype "input"))
      (node (ref "U6") (pin "9") (pinfunction "INTA_9") (pintype "bidirectional"))
    )
    (net (code "59") (name "Net-(U6-OSCI)") (class "Default")
      (node (ref "Q5") (pin "2") (pinfunction "2_2") (pintype "passive"))
      (node (ref "U6") (pin "1") (pinfunction "OSCI_1") (pintype "bidirectional"))
    )
    (net (code "60") (name "Net-(U6-OSCO)") (class "Default")
      (node (ref "Q5") (pin "1") (pinfunction "1_1") (pintype "passive"))
      (node (ref "U6") (pin "2") (pinfunction "OSCO_2") (pintype "bidirectional"))
    )
    (net (code "61") (name "Net-(U6-VBAT)") (class "Default")
      (node (ref "C21") (pin "1") (pinfunction "1_1") (pintype "passive"))
      (node (ref "C23") (pin "1") (pinfunction "1_1") (pintype "passive"))
      (node (ref "R20") (pin "1") (pinfunction "1_1") (pintype "passive"))
      (node (ref "U6") (pin "3") (pinfunction "VBAT_3") (pintype "bidirectional"))
    )
    (net (code "62") (name "SPI0_CE0") (class "Default")
      (node (ref "CTRL1") (pin "5") (pinfunction "CSN_5") (pintype "passive"))
      (node (ref "K1") (pin "24") (pinfunction "24_24") (pintype "passive"))
    )
    (net (code "63") (name "SPI0_CE1") (class "Default")
      (node (ref "CTRL2") (pin "5") (pinfunction "CSN_5") (pintype "passive"))
      (node (ref "K1") (pin "26") (pinfunction "26_26") (pintype "passive"))
    )
    (net (code "64") (name "SPI0_MISO") (class "Default")
      (node (ref "CTRL1") (pin "4") (pinfunction "SDO_4") (pintype "passive"))
      (node (ref "CTRL2") (pin "4") (pinfunction "SDO_4") (pintype "passive"))
      (node (ref "K1") (pin "21") (pinfunction "21_21") (pintype "passive"))
    )
    (net (code "65") (name "SPI0_MOSI") (class "Default")
      (node (ref "CTRL1") (pin "7") (pinfunction "SDI_7") (pintype "passive"))
      (node (ref "CTRL2") (pin "7") (pinfunction "SDI_7") (pintype "passive"))
      (node (ref "K1") (pin "19") (pinfunction "19_19") (pintype "passive"))
    )
    (net (code "66") (name "SPI0_SCLK") (class "Default")
      (node (ref "CTRL1") (pin "6") (pinfunction "SCK_6") (pintype "passive"))
      (node (ref "CTRL2") (pin "6") (pinfunction "SCK_6") (pintype "passive"))
      (node (ref "K1") (pin "23") (pinfunction "23_23") (pintype "passive"))
    )
    (net (code "67") (name "SW") (class "Default")
      (node (ref "L1") (pin "1") (pinfunction "1_1") (pintype "passive"))
      (node (ref "R8") (pin "1") (pinfunction "1_1") (pintype "passive"))
      (node (ref "U3") (pin "8") (pinfunction "SW_8") (pintype "output"))
    )
    (net (code "68") (name "UART_RX") (class "Default")
      (node (ref "K1") (pin "10") (pinfunction "10_10") (pintype "passive"))
    )
    (net (code "69") (name "UART_TX") (class "Default")
      (node (ref "K1") (pin "8") (pinfunction "8_8") (pintype "passive"))
    )
    (net (code "70") (name "unconnected-(CTRL1-DIR-Pad1)") (class "Default")
      (node (ref "CTRL1") (pin "1") (pinfunction "DIR_1") (pintype "passive"))
    )
    (net (code "71") (name "unconnected-(CTRL1-STEP-Pad2)") (class "Default")
      (node (ref "CTRL1") (pin "2") (pinfunction "STEP_2") (pintype "passive"))
    )
    (net (code "72") (name "unconnected-(CTRL2-DIR-Pad1)") (class "Default")
      (node (ref "CTRL2") (pin "1") (pinfunction "DIR_1") (pintype "passive"))
    )
    (net (code "73") (name "unconnected-(CTRL2-STEP-Pad2)") (class "Default")
      (node (ref "CTRL2") (pin "2") (pinfunction "STEP_2") (pintype "passive"))
    )
    (net (code "74") (name "unconnected-(FAN-PadRPM)") (class "Default")
      (node (ref "FAN") (pin "RPM") (pinfunction "RPM_RPM") (pintype "passive"))
    )
    (net (code "75") (name "unconnected-(K1-Pad1)") (class "Default")
      (node (ref "K1") (pin "1") (pinfunction "1_1") (pintype "passive"))
    )
    (net (code "76") (name "unconnected-(U2-NC-PadB1)") (class "Default")
      (node (ref "U2") (pin "B1") (pinfunction "NC_B1") (pintype "passive"))
    )
    (net (code "77") (name "unconnected-(U6-TS-Pad4)") (class "Default")
      (node (ref "U6") (pin "4") (pinfunction "TS_4") (pintype "bidirectional"))
    )
  )
)
